# board.net
KiCad netlist of a schematic drawn in EAGLE
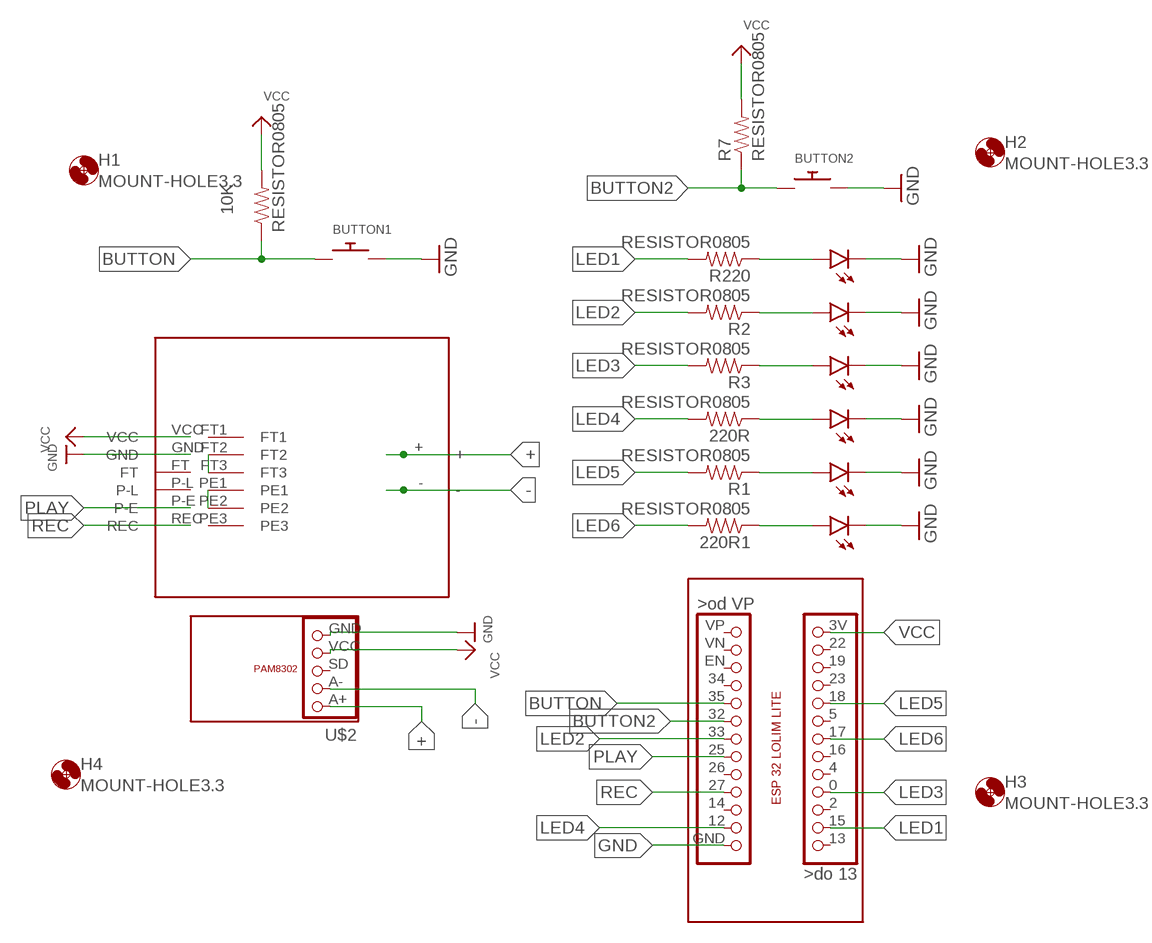
[diagram p0: schematic, sheet 1]

(export (version "E")
  (design (tool "Eeschema 10.0.6"))
  (components
    (comp (ref "10K")
      (value "RESISTOR0805")
      (footprint "eagle-import:R0805")
      (libsource (lib "eagle-import") (part "RESISTOR0805"))
    )
    (comp (ref "220R")
      (value "RESISTOR0805")
      (footprint "eagle-import:R0805")
      (libsource (lib "eagle-import") (part "RESISTOR0805"))
    )
    (comp (ref "220R1")
      (value "RESISTOR0805")
      (footprint "eagle-import:R0805")
      (libsource (lib "eagle-import") (part "RESISTOR0805"))
    )
    (comp (ref "BUTTON1")
      (value "SWITCH_PUSHBUTTONEVQ-PE")
      (footprint "eagle-import:TACT_PANA-EVQ")
      (libsource (lib "eagle-import") (part "SWITCH_PUSHBUTTONEVQ-PE"))
    )
    (comp (ref "BUTTON2")
      (value "SWITCH_PUSHBUTTONEVQ-PE")
      (footprint "eagle-import:TACT_PANA-EVQ")
      (libsource (lib "eagle-import") (part "SWITCH_PUSHBUTTONEVQ-PE"))
    )
    (comp (ref "ESP32")
      (value "NOWA-ESP32")
      (footprint "eagle-import:NOWA-ESP32")
      (libsource (lib "eagle-import") (part "NOWA-ESP32"))
    )
    (comp (ref "H1")
      (value "MOUNT-HOLE3.3")
      (footprint "eagle-import:3,3")
      (libsource (lib "eagle-import") (part "MOUNT-HOLE3.3"))
    )
    (comp (ref "H2")
      (value "MOUNT-HOLE3.3")
      (footprint "eagle-import:3,3")
      (libsource (lib "eagle-import") (part "MOUNT-HOLE3.3"))
    )
    (comp (ref "H3")
      (value "MOUNT-HOLE3.3")
      (footprint "eagle-import:3,3")
      (libsource (lib "eagle-import") (part "MOUNT-HOLE3.3"))
    )
    (comp (ref "H4")
      (value "MOUNT-HOLE3.3")
      (footprint "eagle-import:3,3")
      (libsource (lib "eagle-import") (part "MOUNT-HOLE3.3"))
    )
    (comp (ref "LED1")
      (value "LED5MM")
      (footprint "eagle-import:LED5MM")
      (libsource (lib "eagle-import") (part "LED5MM"))
    )
    (comp (ref "LED2")
      (value "LED5MM")
      (footprint "eagle-import:LED5MM")
      (libsource (lib "eagle-import") (part "LED5MM"))
    )
    (comp (ref "LED3")
      (value "LED5MM")
      (footprint "eagle-import:LED5MM")
      (libsource (lib "eagle-import") (part "LED5MM"))
    )
    (comp (ref "LED4")
      (value "LED5MM")
      (footprint "eagle-import:LED5MM")
      (libsource (lib "eagle-import") (part "LED5MM"))
    )
    (comp (ref "LED5")
      (value "LED5MM")
      (footprint "eagle-import:LED5MM")
      (libsource (lib "eagle-import") (part "LED5MM"))
    )
    (comp (ref "LED6")
      (value "LED5MM")
      (footprint "eagle-import:LED5MM")
      (libsource (lib "eagle-import") (part "LED5MM"))
    )
    (comp (ref "R1")
      (value "RESISTOR0805")
      (footprint "eagle-import:R0805")
      (libsource (lib "eagle-import") (part "RESISTOR0805"))
    )
    (comp (ref "R2")
      (value "RESISTOR0805")
      (footprint "eagle-import:R0805")
      (libsource (lib "eagle-import") (part "RESISTOR0805"))
    )
    (comp (ref "R3")
      (value "RESISTOR0805")
      (footprint "eagle-import:R0805")
      (libsource (lib "eagle-import") (part "RESISTOR0805"))
    )
    (comp (ref "R7")
      (value "RESISTOR0805")
      (footprint "eagle-import:R0805")
      (libsource (lib "eagle-import") (part "RESISTOR0805"))
    )
    (comp (ref "R220")
      (value "RESISTOR0805")
      (footprint "eagle-import:R0805")
      (libsource (lib "eagle-import") (part "RESISTOR0805"))
    )
    (comp (ref "U$2")
      (value "NOWA-PAM8302")
      (footprint "eagle-import:NOWA-PAM8302")
      (libsource (lib "eagle-import") (part "NOWA-PAM8302"))
    )
    (comp (ref "U$7")
      (value "NOWA-ISD1820")
      (footprint "eagle-import:NOWA-ISD1820")
      (libsource (lib "eagle-import") (part "NOWA-ISD1820"))
    )
  )
  (nets
    (net (code "1") (name "+") (class "Default")
      (node (ref "U$2") (pin "A+") (pinfunction "A+_A+") (pintype "passive"))
      (node (ref "U$7") (pin "+") (pinfunction "+_+") (pintype "bidirectional"))
    )
    (net (code "2") (name "-") (class "Default")
      (node (ref "U$2") (pin "A-") (pinfunction "A-_A-") (pintype "passive"))
      (node (ref "U$7") (pin "-") (pinfunction "-_-") (pintype "bidirectional"))
    )
    (net (code "3") (name "BUTTON") (class "Default")
      (node (ref "10K") (pin "1") (pinfunction "1_1") (pintype "passive"))
      (node (ref "BUTTON1") (pin "P$1") (pinfunction "P$1_P$1") (pintype "passive"))
      (node (ref "ESP32") (pin "35") (pinfunction "35_35") (pintype "passive"))
    )
    (net (code "4") (name "BUTTON2") (class "Default")
      (node (ref "BUTTON2") (pin "P$1") (pinfunction "P$1_P$1") (pintype "passive"))
      (node (ref "ESP32") (pin "32") (pinfunction "32_32") (pintype "passive"))
      (node (ref "R7") (pin "1") (pinfunction "1_1") (pintype "passive"))
    )
    (net (code "5") (name "GND") (class "Default")
      (node (ref "BUTTON1") (pin "P$2") (pinfunction "P$2_P$2") (pintype "passive"))
      (node (ref "BUTTON2") (pin "P$2") (pinfunction "P$2_P$2") (pintype "passive"))
      (node (ref "ESP32") (pin "GND") (pinfunction "GND_GND") (pintype "passive"))
      (node (ref "LED1") (pin "K") (pinfunction "C_K") (pintype "passive"))
      (node (ref "LED2") (pin "K") (pinfunction "C_K") (pintype "passive"))
      (node (ref "LED3") (pin "K") (pinfunction "C_K") (pintype "passive"))
      (node (ref "LED4") (pin "K") (pinfunction "C_K") (pintype "passive"))
      (node (ref "LED5") (pin "K") (pinfunction "C_K") (pintype "passive"))
      (node (ref "LED6") (pin "K") (pinfunction "C_K") (pintype "passive"))
      (node (ref "U$2") (pin "GND") (pinfunction "GND_GND") (pintype "passive"))
      (node (ref "U$7") (pin "GND") (pinfunction "GND_GND") (pintype "bidirectional"))
    )
    (net (code "6") (name "LED1") (class "Default")
      (node (ref "ESP32") (pin "15") (pinfunction "15_15") (pintype "passive"))
      (node (ref "R220") (pin "2") (pinfunction "2_2") (pintype "passive"))
    )
    (net (code "7") (name "LED2") (class "Default")
      (node (ref "ESP32") (pin "33") (pinfunction "33_33") (pintype "passive"))
      (node (ref "R2") (pin "2") (pinfunction "2_2") (pintype "passive"))
    )
    (net (code "8") (name "LED3") (class "Default")
      (node (ref "ESP32") (pin "0") (pinfunction "0_0") (pintype "passive"))
      (node (ref "R3") (pin "2") (pinfunction "2_2") (pintype "passive"))
    )
    (net (code "9") (name "LED4") (class "Default")
      (node (ref "220R") (pin "2") (pinfunction "2_2") (pintype "passive"))
      (node (ref "ESP32") (pin "12") (pinfunction "12_12") (pintype "passive"))
    )
    (net (code "10") (name "LED5") (class "Default")
      (node (ref "ESP32") (pin "18") (pinfunction "18_18") (pintype "passive"))
      (node (ref "R1") (pin "2") (pinfunction "2_2") (pintype "passive"))
    )
    (net (code "11") (name "LED6") (class "Default")
      (node (ref "220R1") (pin "2") (pinfunction "2_2") (pintype "passive"))
      (node (ref "ESP32") (pin "17") (pinfunction "17_17") (pintype "passive"))
    )
    (net (code "12") (name "Net-(220R-Pad1)") (class "Default")
      (node (ref "220R") (pin "1") (pinfunction "1_1") (pintype "passive"))
      (node (ref "LED1") (pin "A") (pinfunction "A_A") (pintype "passive"))
    )
    (net (code "13") (name "Net-(220R1-Pad1)") (class "Default")
      (node (ref "220R1") (pin "1") (pinfunction "1_1") (pintype "passive"))
      (node (ref "LED6") (pin "A") (pinfunction "A_A") (pintype "passive"))
    )
    (net (code "14") (name "Net-(LED2-PadA)") (class "Default")
      (node (ref "LED2") (pin "A") (pinfunction "A_A") (pintype "passive"))
      (node (ref "R220") (pin "1") (pinfunction "1_1") (pintype "passive"))
    )
    (net (code "15") (name "Net-(LED3-PadA)") (class "Default")
      (node (ref "LED3") (pin "A") (pinfunction "A_A") (pintype "passive"))
      (node (ref "R2") (pin "1") (pinfunction "1_1") (pintype "passive"))
    )
    (net (code "16") (name "Net-(LED4-PadA)") (class "Default")
      (node (ref "LED4") (pin "A") (pinfunction "A_A") (pintype "passive"))
      (node (ref "R3") (pin "1") (pinfunction "1_1") (pintype "passive"))
    )
    (net (code "17") (name "Net-(LED5-PadA)") (class "Default")
      (node (ref "LED5") (pin "A") (pinfunction "A_A") (pintype "passive"))
      (node (ref "R1") (pin "1") (pinfunction "1_1") (pintype "passive"))
    )
    (net (code "18") (name "Net-(U$7-PadFT2)") (class "Default")
      (node (ref "U$7") (pin "FT2") (pinfunction "FT2_FT2") (pintype "bidirectional"))
      (node (ref "U$7") (pin "FT3") (pinfunction "FT3_FT3") (pintype "bidirectional"))
    )
    (net (code "19") (name "Net-(U$7-PadPE1)") (class "Default")
      (node (ref "U$7") (pin "PE1") (pinfunction "PE1_PE1") (pintype "bidirectional"))
      (node (ref "U$7") (pin "PE2") (pinfunction "PE2_PE2") (pintype "bidirectional"))
    )
    (net (code "20") (name "PLAY") (class "Default")
      (node (ref "ESP32") (pin "25") (pinfunction "25_25") (pintype "passive"))
      (node (ref "U$7") (pin "P-E") (pinfunction "P-E_P-E") (pintype "bidirectional"))
    )
    (net (code "21") (name "REC") (class "Default")
      (node (ref "ESP32") (pin "27") (pinfunction "27_27") (pintype "passive"))
      (node (ref "U$7") (pin "REC") (pinfunction "REC_REC") (pintype "bidirectional"))
    )
    (net (code "22") (name "VCC") (class "Default")
      (node (ref "10K") (pin "2") (pinfunction "2_2") (pintype "passive"))
      (node (ref "ESP32") (pin "3V") (pinfunction "3V_3V") (pintype "passive"))
      (node (ref "R7") (pin "2") (pinfunction "2_2") (pintype "passive"))
      (node (ref "U$2") (pin "VCC") (pinfunction "VCC_VCC") (pintype "passive"))
      (node (ref "U$7") (pin "VCC") (pinfunction "VCC_VCC") (pintype "bidirectional"))
    )
    (net (code "23") (name "unconnected-(ESP32-Pad2)") (class "Default")
      (node (ref "ESP32") (pin "2") (pinfunction "2_2") (pintype "passive"))
    )
    (net (code "24") (name "unconnected-(ESP32-Pad4)") (class "Default")
      (node (ref "ESP32") (pin "4") (pinfunction "4_4") (pintype "passive"))
    )
    (net (code "25") (name "unconnected-(ESP32-Pad5)") (class "Default")
      (node (ref "ESP32") (pin "5") (pinfunction "5_5") (pintype "passive"))
    )
    (net (code "26") (name "unconnected-(ESP32-Pad13)") (class "Default")
      (node (ref "ESP32") (pin "13") (pinfunction "13_13") (pintype "passive"))
    )
    (net (code "27") (name "unconnected-(ESP32-Pad14)") (class "Default")
      (node (ref "ESP32") (pin "14") (pinfunction "14_14") (pintype "passive"))
    )
    (net (code "28") (name "unconnected-(ESP32-Pad16)") (class "Default")
      (node (ref "ESP32") (pin "16") (pinfunction "16_16") (pintype "passive"))
    )
    (net (code "29") (name "unconnected-(ESP32-Pad19)") (class "Default")
      (node (ref "ESP32") (pin "19") (pinfunction "19_19") (pintype "passive"))
    )
    (net (code "30") (name "unconnected-(ESP32-Pad22)") (class "Default")
      (node (ref "ESP32") (pin "22") (pinfunction "22_22") (pintype "passive"))
    )
    (net (code "31") (name "unconnected-(ESP32-Pad23)") (class "Default")
      (node (ref "ESP32") (pin "23") (pinfunction "23_23") (pintype "passive"))
    )
    (net (code "32") (name "unconnected-(ESP32-Pad26)") (class "Default")
      (node (ref "ESP32") (pin "26") (pinfunction "26_26") (pintype "passive"))
    )
    (net (code "33") (name "unconnected-(ESP32-Pad34)") (class "Default")
      (node (ref "ESP32") (pin "34") (pinfunction "34_34") (pintype "passive"))
    )
    (net (code "34") (name "unconnected-(ESP32-PadEN)") (class "Default")
      (node (ref "ESP32") (pin "EN") (pinfunction "EN_EN") (pintype "passive"))
    )
    (net (code "35") (name "unconnected-(ESP32-PadVN)") (class "Default")
      (node (ref "ESP32") (pin "VN") (pinfunction "VN_VN") (pintype "passive"))
    )
    (net (code "36") (name "unconnected-(ESP32-PadVP)") (class "Default")
      (node (ref "ESP32") (pin "VP") (pinfunction "VP_VP") (pintype "passive"))
    )
    (net (code "37") (name "unconnected-(U$2-PadSD)") (class "Default")
      (node (ref "U$2") (pin "SD") (pinfunction "SD_SD") (pintype "passive"))
    )
    (net (code "38") (name "unconnected-(U$7-PadFT)") (class "Default")
      (node (ref "U$7") (pin "FT") (pinfunction "FT_FT") (pintype "bidirectional"))
    )
    (net (code "39") (name "unconnected-(U$7-PadFT1)") (class "Default")
      (node (ref "U$7") (pin "FT1") (pinfunction "FT1_FT1") (pintype "bidirectional"))
    )
    (net (code "40") (name "unconnected-(U$7-PadP-L)") (class "Default")
      (node (ref "U$7") (pin "P-L") (pinfunction "P-L_P-L") (pintype "bidirectional"))
    )
    (net (code "41") (name "unconnected-(U$7-PadPE3)") (class "Default")
      (node (ref "U$7") (pin "PE3") (pinfunction "PE3_PE3") (pintype "bidirectional"))
    )
  )
)
